# Steering_Wheel_V2_3.net
KiCad netlist of a schematic drawn in EAGLE
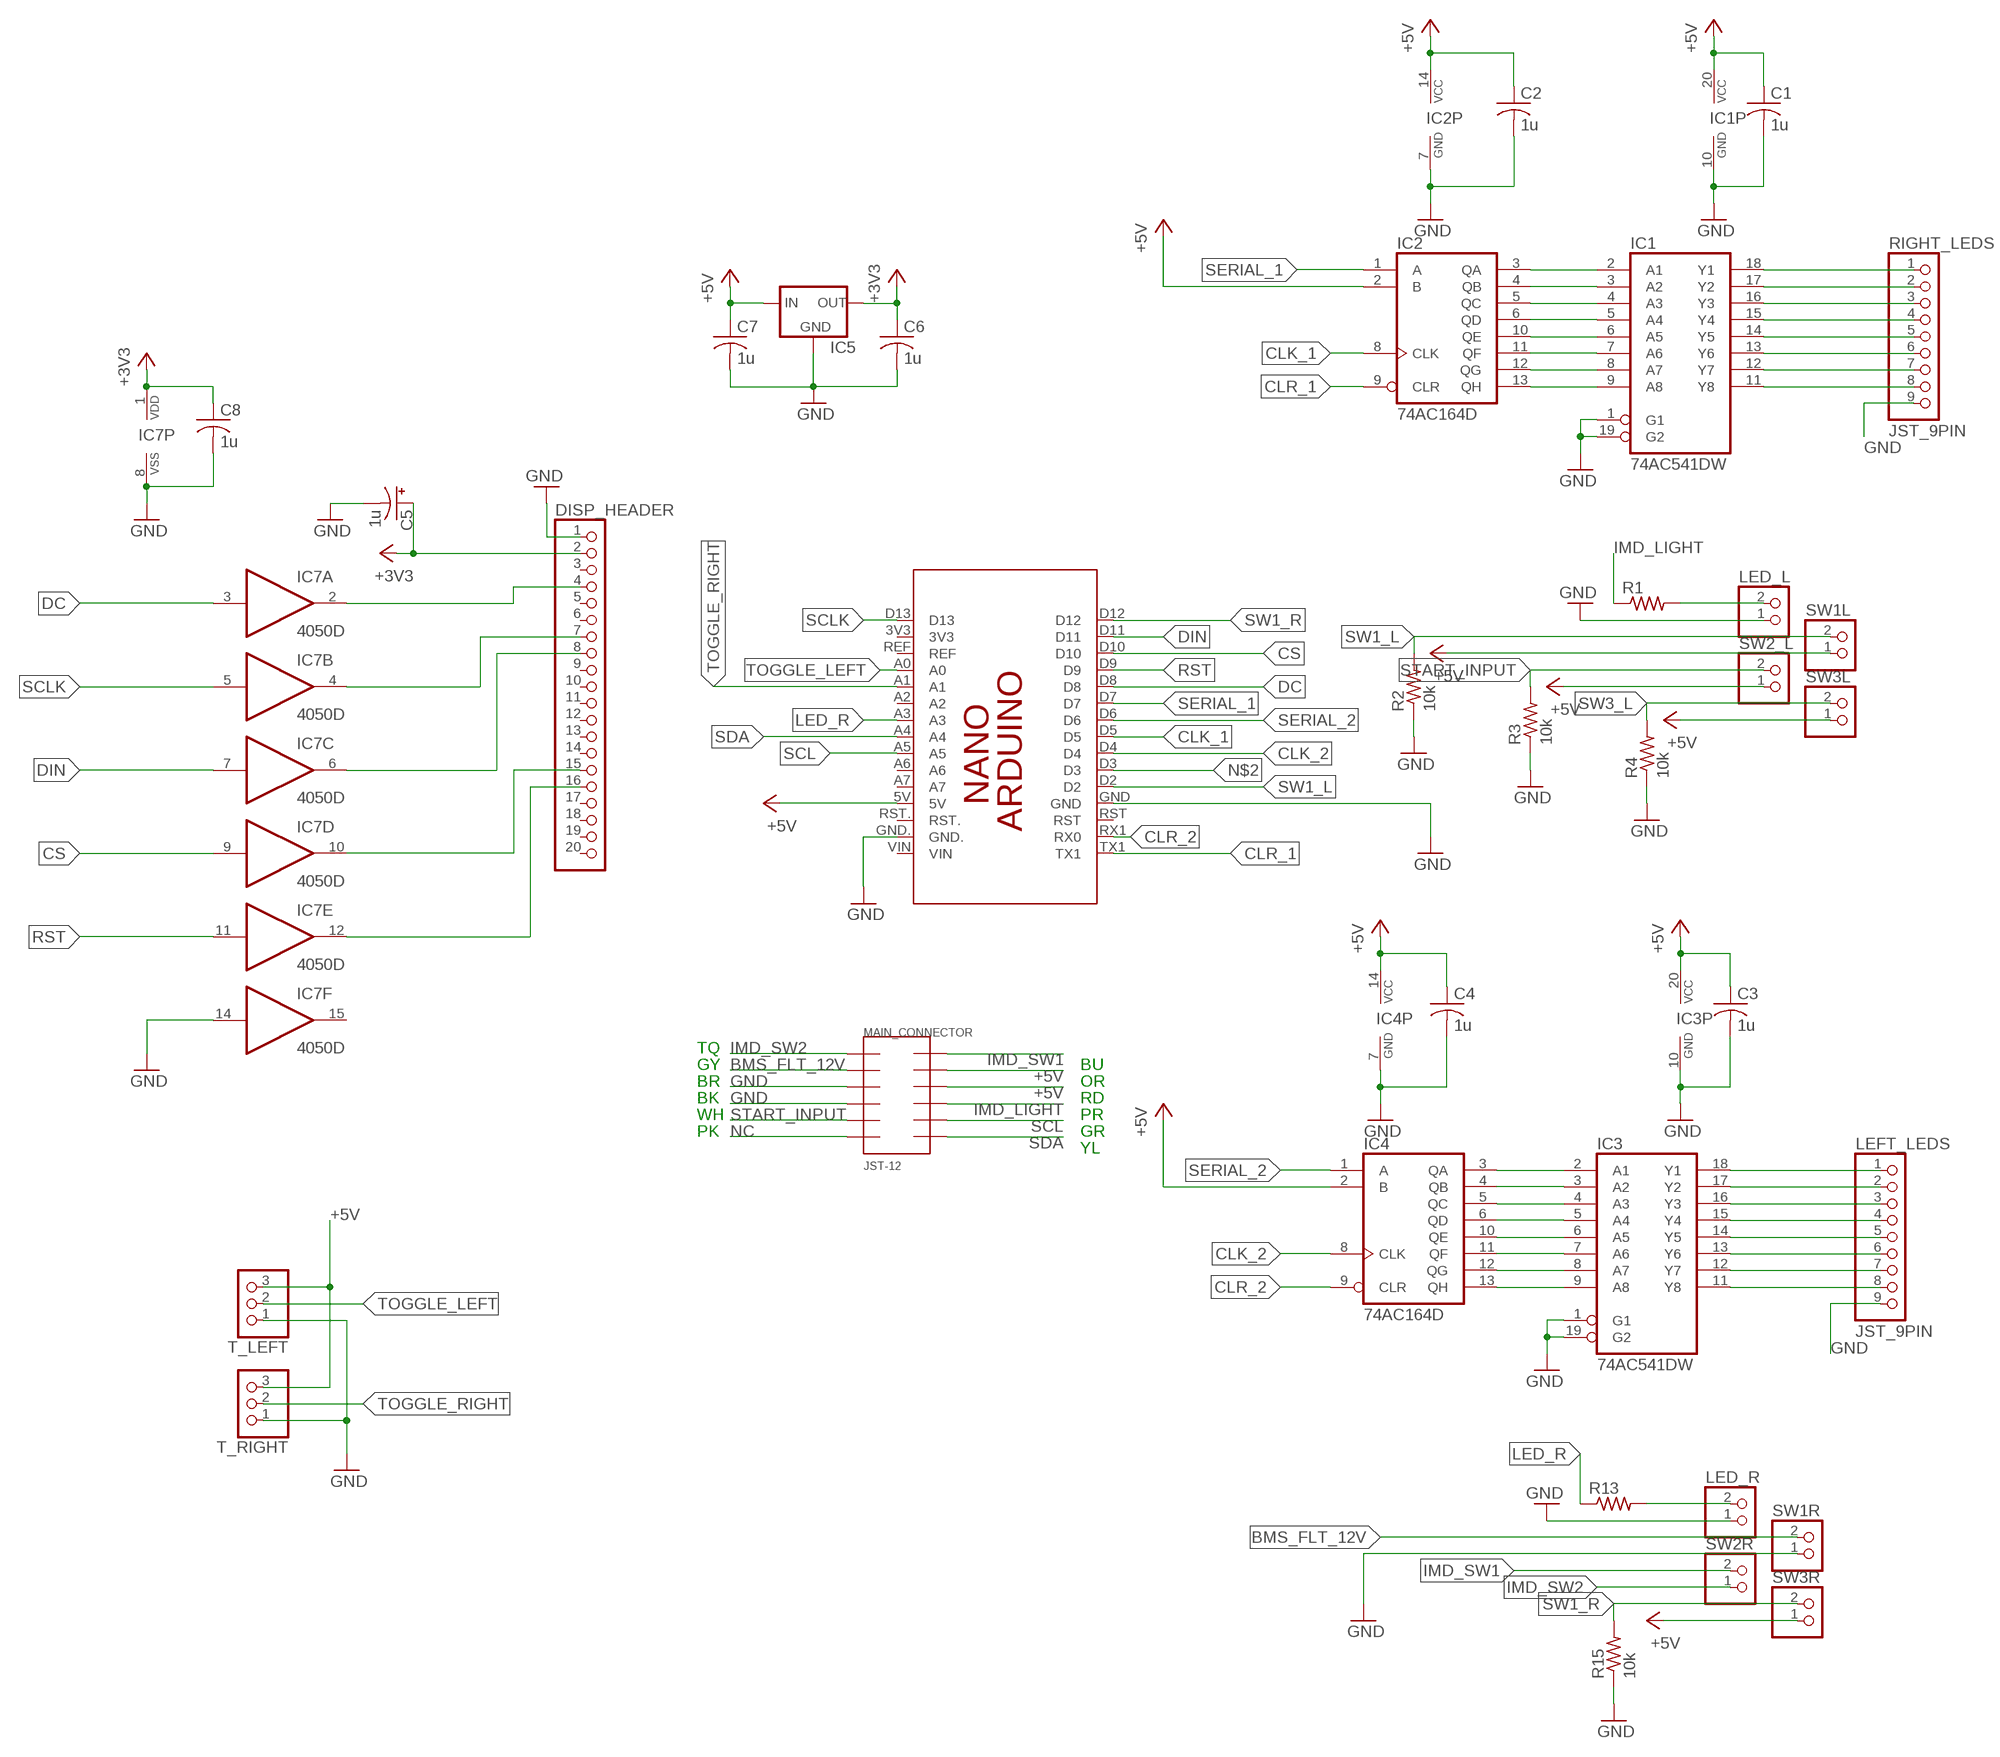
[diagram p0: schematic, sheet 1]

(export (version "E")
  (design (tool "Eeschema 10.0.6"))
  (components
    (comp (ref "C1")
      (value "1u")
      (footprint "eagle-import:C1206")
      (libsource (lib "eagle-import") (part "C-USC1206"))
    )
    (comp (ref "C2")
      (value "1u")
      (footprint "eagle-import:C1206")
      (libsource (lib "eagle-import") (part "C-USC1206"))
    )
    (comp (ref "C3")
      (value "1u")
      (footprint "eagle-import:C1206")
      (libsource (lib "eagle-import") (part "C-USC1206"))
    )
    (comp (ref "C4")
      (value "1u")
      (footprint "eagle-import:C1206")
      (libsource (lib "eagle-import") (part "C-USC1206"))
    )
    (comp (ref "C5")
      (value "1u")
      (footprint "eagle-import:E3,5-8")
      (libsource (lib "eagle-import") (part "CPOL-USE3.5-8"))
    )
    (comp (ref "C6")
      (value "1u")
      (footprint "eagle-import:C1206")
      (libsource (lib "eagle-import") (part "C-USC1206"))
    )
    (comp (ref "C7")
      (value "1u")
      (footprint "eagle-import:C1206")
      (libsource (lib "eagle-import") (part "C-USC1206"))
    )
    (comp (ref "C8")
      (value "1u")
      (footprint "eagle-import:C1206")
      (libsource (lib "eagle-import") (part "C-USC1206"))
    )
    (comp (ref "DISP_HEADER")
      (value "PINHD-1X20")
      (footprint "eagle-import:1X20")
      (libsource (lib "eagle-import") (part "PINHD-1X20"))
    )
    (comp (ref "IC1")
      (value "74AC541DW")
      (footprint "eagle-import:SO20W")
      (libsource (lib "eagle-import") (part "74541DWAC"))
    )
    (comp (ref "IC2")
      (value "74AC164D")
      (footprint "eagle-import:SO14")
      (libsource (lib "eagle-import") (part "74164DAC"))
    )
    (comp (ref "IC3")
      (value "74AC541DW")
      (footprint "eagle-import:SO20W")
      (libsource (lib "eagle-import") (part "74541DWAC"))
    )
    (comp (ref "IC4")
      (value "74AC164D")
      (footprint "eagle-import:SO14")
      (libsource (lib "eagle-import") (part "74164DAC"))
    )
    (comp (ref "IC5")
      (value "78XXL")
      (footprint "eagle-import:78XXL")
      (libsource (lib "eagle-import") (part "78XXL"))
    )
    (comp (ref "IC7")
      (value "4050D")
      (footprint "eagle-import:SO16")
      (libsource (lib "eagle-import") (part "4050D"))
    )
    (comp (ref "LED_L")
      (value "JST_2PIN-THM")
      (footprint "eagle-import:JST-PH-2-THM")
      (libsource (lib "eagle-import") (part "JST_2PIN-THM"))
    )
    (comp (ref "LED_R")
      (value "JST_2PIN-THM")
      (footprint "eagle-import:JST-PH-2-THM")
      (libsource (lib "eagle-import") (part "JST_2PIN-THM"))
    )
    (comp (ref "LEFT_LEDS")
      (value "JST_9PIN")
      (footprint "eagle-import:JST-PH-9-THM")
      (libsource (lib "eagle-import") (part "JST_9PIN"))
    )
    (comp (ref "MAIN_CONNECTOR")
      (value "JST-12")
      (footprint "eagle-import:PHD-12")
      (libsource (lib "eagle-import") (part "JST-12"))
    )
    (comp (ref "PCB1")
      (value "ARDUINO_NANO")
      (footprint "eagle-import:ARDUINO_NANO")
      (libsource (lib "eagle-import") (part "ARDUINO_NANO"))
    )
    (comp (ref "R1")
      (value "R-US_M1206")
      (footprint "eagle-import:M1206")
      (libsource (lib "eagle-import") (part "R-US_M1206"))
    )
    (comp (ref "R2")
      (value "10k")
      (footprint "eagle-import:M1206")
      (libsource (lib "eagle-import") (part "R-US_M1206"))
    )
    (comp (ref "R3")
      (value "10k")
      (footprint "eagle-import:M1206")
      (libsource (lib "eagle-import") (part "R-US_M1206"))
    )
    (comp (ref "R4")
      (value "10k")
      (footprint "eagle-import:M1206")
      (libsource (lib "eagle-import") (part "R-US_M1206"))
    )
    (comp (ref "R13")
      (value "R-US_M1206")
      (footprint "eagle-import:M1206")
      (libsource (lib "eagle-import") (part "R-US_M1206"))
    )
    (comp (ref "R15")
      (value "10k")
      (footprint "eagle-import:M1206")
      (libsource (lib "eagle-import") (part "R-US_M1206"))
    )
    (comp (ref "RIGHT_LEDS")
      (value "JST_9PIN")
      (footprint "eagle-import:JST-PH-9-THM")
      (libsource (lib "eagle-import") (part "JST_9PIN"))
    )
    (comp (ref "SW1L")
      (value "JST_2PIN-THM")
      (footprint "eagle-import:JST-PH-2-THM")
      (libsource (lib "eagle-import") (part "JST_2PIN-THM"))
    )
    (comp (ref "SW1R")
      (value "JST_2PIN-THM")
      (footprint "eagle-import:JST-PH-2-THM")
      (libsource (lib "eagle-import") (part "JST_2PIN-THM"))
    )
    (comp (ref "SW2R")
      (value "JST_2PIN-THM")
      (footprint "eagle-import:JST-PH-2-THM")
      (libsource (lib "eagle-import") (part "JST_2PIN-THM"))
    )
    (comp (ref "SW2_L")
      (value "JST_2PIN-THM")
      (footprint "eagle-import:JST-PH-2-THM")
      (libsource (lib "eagle-import") (part "JST_2PIN-THM"))
    )
    (comp (ref "SW3L")
      (value "JST_2PIN-THM")
      (footprint "eagle-import:JST-PH-2-THM")
      (libsource (lib "eagle-import") (part "JST_2PIN-THM"))
    )
    (comp (ref "SW3R")
      (value "JST_2PIN-THM")
      (footprint "eagle-import:JST-PH-2-THM")
      (libsource (lib "eagle-import") (part "JST_2PIN-THM"))
    )
    (comp (ref "T_LEFT")
      (value "JST_3PIN")
      (footprint "eagle-import:JST-PH-3-THM")
      (libsource (lib "eagle-import") (part "JST_3PIN"))
    )
    (comp (ref "T_RIGHT")
      (value "JST_3PIN")
      (footprint "eagle-import:JST-PH-3-THM")
      (libsource (lib "eagle-import") (part "JST_3PIN"))
    )
  )
  (nets
    (net (code "1") (name "+3V3") (class "Default")
      (node (ref "C5") (pin "+") (pinfunction "+_+") (pintype "passive"))
      (node (ref "C6") (pin "1") (pinfunction "1_1") (pintype "passive"))
      (node (ref "C8") (pin "1") (pinfunction "1_1") (pintype "passive"))
      (node (ref "DISP_HEADER") (pin "2") (pinfunction "2_2") (pintype "passive"))
      (node (ref "IC5") (pin "OUT") (pinfunction "OUT_OUT") (pintype "passive"))
      (node (ref "IC7") (pin "1") (pinfunction "VDD_1") (pintype "power_in"))
    )
    (net (code "2") (name "+5V") (class "Default")
      (node (ref "C1") (pin "1") (pinfunction "1_1") (pintype "passive"))
      (node (ref "C2") (pin "1") (pinfunction "1_1") (pintype "passive"))
      (node (ref "C3") (pin "1") (pinfunction "1_1") (pintype "passive"))
      (node (ref "C4") (pin "1") (pinfunction "1_1") (pintype "passive"))
      (node (ref "C7") (pin "1") (pinfunction "1_1") (pintype "passive"))
      (node (ref "IC1") (pin "20") (pinfunction "VCC_20") (pintype "power_in"))
      (node (ref "IC2") (pin "14") (pinfunction "VCC_14") (pintype "power_in"))
      (node (ref "IC2") (pin "2") (pinfunction "B_2") (pintype "input"))
      (node (ref "IC3") (pin "20") (pinfunction "VCC_20") (pintype "power_in"))
      (node (ref "IC4") (pin "14") (pinfunction "VCC_14") (pintype "power_in"))
      (node (ref "IC4") (pin "2") (pinfunction "B_2") (pintype "input"))
      (node (ref "IC5") (pin "IN") (pinfunction "IN_IN") (pintype "input"))
      (node (ref "MAIN_CONNECTOR") (pin "10") (pinfunction "10_10") (pintype "bidirectional"))
      (node (ref "MAIN_CONNECTOR") (pin "11") (pinfunction "11_11") (pintype "bidirectional"))
      (node (ref "PCB1") (pin "5V") (pinfunction "5V_5V") (pintype "bidirectional"))
      (node (ref "SW1L") (pin "1") (pinfunction "2_1") (pintype "passive"))
      (node (ref "SW2_L") (pin "1") (pinfunction "2_1") (pintype "passive"))
      (node (ref "SW3L") (pin "1") (pinfunction "2_1") (pintype "passive"))
      (node (ref "SW3R") (pin "1") (pinfunction "2_1") (pintype "passive"))
      (node (ref "T_LEFT") (pin "3") (pinfunction "3_3") (pintype "passive"))
      (node (ref "T_RIGHT") (pin "3") (pinfunction "3_3") (pintype "passive"))
    )
    (net (code "3") (name "/IMD_LIGHT") (class "Default")
      (node (ref "MAIN_CONNECTOR") (pin "9") (pinfunction "9_9") (pintype "bidirectional"))
      (node (ref "R1") (pin "1") (pinfunction "1_1") (pintype "passive"))
    )
    (net (code "4") (name "/NC") (class "Default")
      (node (ref "MAIN_CONNECTOR") (pin "6") (pinfunction "6_6") (pintype "bidirectional"))
    )
    (net (code "5") (name "BMS_FLT_12V") (class "Default")
      (node (ref "MAIN_CONNECTOR") (pin "2") (pinfunction "2_2") (pintype "bidirectional"))
      (node (ref "SW1R") (pin "2") (pinfunction "1_2") (pintype "passive"))
    )
    (net (code "6") (name "CLK_1") (class "Default")
      (node (ref "IC2") (pin "8") (pinfunction "CLK_8") (pintype "input"))
      (node (ref "PCB1") (pin "D5") (pinfunction "D5_D5") (pintype "bidirectional"))
    )
    (net (code "7") (name "CLK_2") (class "Default")
      (node (ref "IC4") (pin "8") (pinfunction "CLK_8") (pintype "input"))
      (node (ref "PCB1") (pin "D4") (pinfunction "D4_D4") (pintype "bidirectional"))
    )
    (net (code "8") (name "CLR_1") (class "Default")
      (node (ref "IC2") (pin "9") (pinfunction "CLR_9") (pintype "input"))
      (node (ref "PCB1") (pin "TX1") (pinfunction "TX1_TX1") (pintype "bidirectional"))
    )
    (net (code "9") (name "CLR_2") (class "Default")
      (node (ref "IC4") (pin "9") (pinfunction "CLR_9") (pintype "input"))
      (node (ref "PCB1") (pin "RX1") (pinfunction "RX0_RX1") (pintype "bidirectional"))
    )
    (net (code "10") (name "CS") (class "Default")
      (node (ref "IC7") (pin "9") (pinfunction "I_9") (pintype "input"))
      (node (ref "PCB1") (pin "D10") (pinfunction "D10_D10") (pintype "bidirectional"))
    )
    (net (code "11") (name "DC") (class "Default")
      (node (ref "IC7") (pin "3") (pinfunction "I_3") (pintype "input"))
      (node (ref "PCB1") (pin "D8") (pinfunction "D8_D8") (pintype "bidirectional"))
    )
    (net (code "12") (name "DIN") (class "Default")
      (node (ref "IC7") (pin "7") (pinfunction "I_7") (pintype "input"))
      (node (ref "PCB1") (pin "D11") (pinfunction "D11_D11") (pintype "bidirectional"))
    )
    (net (code "13") (name "GND") (class "Default")
      (node (ref "C1") (pin "2") (pinfunction "2_2") (pintype "passive"))
      (node (ref "C2") (pin "2") (pinfunction "2_2") (pintype "passive"))
      (node (ref "C3") (pin "2") (pinfunction "2_2") (pintype "passive"))
      (node (ref "C4") (pin "2") (pinfunction "2_2") (pintype "passive"))
      (node (ref "C5") (pin "-") (pinfunction "-_-") (pintype "passive"))
      (node (ref "C6") (pin "2") (pinfunction "2_2") (pintype "passive"))
      (node (ref "C7") (pin "2") (pinfunction "2_2") (pintype "passive"))
      (node (ref "C8") (pin "2") (pinfunction "2_2") (pintype "passive"))
      (node (ref "DISP_HEADER") (pin "1") (pinfunction "1_1") (pintype "passive"))
      (node (ref "IC1") (pin "1") (pinfunction "G1_1") (pintype "input"))
      (node (ref "IC1") (pin "10") (pinfunction "GND_10") (pintype "power_in"))
      (node (ref "IC1") (pin "19") (pinfunction "G2_19") (pintype "input"))
      (node (ref "IC2") (pin "7") (pinfunction "GND_7") (pintype "power_in"))
      (node (ref "IC3") (pin "1") (pinfunction "G1_1") (pintype "input"))
      (node (ref "IC3") (pin "10") (pinfunction "GND_10") (pintype "power_in"))
      (node (ref "IC3") (pin "19") (pinfunction "G2_19") (pintype "input"))
      (node (ref "IC4") (pin "7") (pinfunction "GND_7") (pintype "power_in"))
      (node (ref "IC5") (pin "GND") (pinfunction "GND_GND") (pintype "input"))
      (node (ref "IC7") (pin "14") (pinfunction "I_14") (pintype "input"))
      (node (ref "IC7") (pin "8") (pinfunction "VSS_8") (pintype "power_in"))
      (node (ref "LED_L") (pin "1") (pinfunction "2_1") (pintype "passive"))
      (node (ref "LED_R") (pin "1") (pinfunction "2_1") (pintype "passive"))
      (node (ref "LEFT_LEDS") (pin "9") (pinfunction "9_9") (pintype "passive"))
      (node (ref "MAIN_CONNECTOR") (pin "3") (pinfunction "3_3") (pintype "bidirectional"))
      (node (ref "MAIN_CONNECTOR") (pin "4") (pinfunction "4_4") (pintype "bidirectional"))
      (node (ref "PCB1") (pin "GND") (pinfunction "GND_GND") (pintype "bidirectional"))
      (node (ref "PCB1") (pin "GND.") (pinfunction "GND._GND.") (pintype "bidirectional"))
      (node (ref "R15") (pin "1") (pinfunction "1_1") (pintype "passive"))
      (node (ref "R2") (pin "1") (pinfunction "1_1") (pintype "passive"))
      (node (ref "R3") (pin "1") (pinfunction "1_1") (pintype "passive"))
      (node (ref "R4") (pin "1") (pinfunction "1_1") (pintype "passive"))
      (node (ref "RIGHT_LEDS") (pin "9") (pinfunction "9_9") (pintype "passive"))
      (node (ref "SW1R") (pin "1") (pinfunction "2_1") (pintype "passive"))
      (node (ref "T_LEFT") (pin "1") (pinfunction "1_1") (pintype "passive"))
      (node (ref "T_RIGHT") (pin "1") (pinfunction "1_1") (pintype "passive"))
    )
    (net (code "14") (name "IMD_SW1") (class "Default")
      (node (ref "MAIN_CONNECTOR") (pin "12") (pinfunction "12_12") (pintype "bidirectional"))
      (node (ref "SW2R") (pin "2") (pinfunction "1_2") (pintype "passive"))
    )
    (net (code "15") (name "IMD_SW2") (class "Default")
      (node (ref "MAIN_CONNECTOR") (pin "1") (pinfunction "1_1") (pintype "bidirectional"))
      (node (ref "SW2R") (pin "1") (pinfunction "2_1") (pintype "passive"))
    )
    (net (code "16") (name "LED_R") (class "Default")
      (node (ref "PCB1") (pin "A3") (pinfunction "A3_A3") (pintype "bidirectional"))
      (node (ref "R13") (pin "1") (pinfunction "1_1") (pintype "passive"))
    )
    (net (code "17") (name "N$2") (class "Default")
      (node (ref "PCB1") (pin "D3") (pinfunction "D3_D3") (pintype "bidirectional"))
    )
    (net (code "18") (name "Net-(IC1A-A1)") (class "Default")
      (node (ref "IC1") (pin "2") (pinfunction "A1_2") (pintype "input"))
      (node (ref "IC2") (pin "3") (pinfunction "QA_3") (pintype "output"))
    )
    (net (code "19") (name "Net-(IC1A-A2)") (class "Default")
      (node (ref "IC1") (pin "3") (pinfunction "A2_3") (pintype "input"))
      (node (ref "IC2") (pin "4") (pinfunction "QB_4") (pintype "output"))
    )
    (net (code "20") (name "Net-(IC1A-A3)") (class "Default")
      (node (ref "IC1") (pin "4") (pinfunction "A3_4") (pintype "input"))
      (node (ref "IC2") (pin "5") (pinfunction "QC_5") (pintype "output"))
    )
    (net (code "21") (name "Net-(IC1A-A4)") (class "Default")
      (node (ref "IC1") (pin "5") (pinfunction "A4_5") (pintype "input"))
      (node (ref "IC2") (pin "6") (pinfunction "QD_6") (pintype "output"))
    )
    (net (code "22") (name "Net-(IC1A-A5)") (class "Default")
      (node (ref "IC1") (pin "6") (pinfunction "A5_6") (pintype "input"))
      (node (ref "IC2") (pin "10") (pinfunction "QE_10") (pintype "output"))
    )
    (net (code "23") (name "Net-(IC1A-A6)") (class "Default")
      (node (ref "IC1") (pin "7") (pinfunction "A6_7") (pintype "input"))
      (node (ref "IC2") (pin "11") (pinfunction "QF_11") (pintype "output"))
    )
    (net (code "24") (name "Net-(IC1A-A7)") (class "Default")
      (node (ref "IC1") (pin "8") (pinfunction "A7_8") (pintype "input"))
      (node (ref "IC2") (pin "12") (pinfunction "QG_12") (pintype "output"))
    )
    (net (code "25") (name "Net-(IC1A-A8)") (class "Default")
      (node (ref "IC1") (pin "9") (pinfunction "A8_9") (pintype "input"))
      (node (ref "IC2") (pin "13") (pinfunction "QH_13") (pintype "output"))
    )
    (net (code "26") (name "Net-(IC1A-Y1)") (class "Default")
      (node (ref "IC1") (pin "18") (pinfunction "Y1_18") (pintype "tri_state"))
      (node (ref "RIGHT_LEDS") (pin "1") (pinfunction "1_1") (pintype "passive"))
    )
    (net (code "27") (name "Net-(IC1A-Y2)") (class "Default")
      (node (ref "IC1") (pin "17") (pinfunction "Y2_17") (pintype "tri_state"))
      (node (ref "RIGHT_LEDS") (pin "2") (pinfunction "2_2") (pintype "passive"))
    )
    (net (code "28") (name "Net-(IC1A-Y3)") (class "Default")
      (node (ref "IC1") (pin "16") (pinfunction "Y3_16") (pintype "tri_state"))
      (node (ref "RIGHT_LEDS") (pin "3") (pinfunction "3_3") (pintype "passive"))
    )
    (net (code "29") (name "Net-(IC1A-Y4)") (class "Default")
      (node (ref "IC1") (pin "15") (pinfunction "Y4_15") (pintype "tri_state"))
      (node (ref "RIGHT_LEDS") (pin "4") (pinfunction "4_4") (pintype "passive"))
    )
    (net (code "30") (name "Net-(IC1A-Y5)") (class "Default")
      (node (ref "IC1") (pin "14") (pinfunction "Y5_14") (pintype "tri_state"))
      (node (ref "RIGHT_LEDS") (pin "5") (pinfunction "5_5") (pintype "passive"))
    )
    (net (code "31") (name "Net-(IC1A-Y6)") (class "Default")
      (node (ref "IC1") (pin "13") (pinfunction "Y6_13") (pintype "tri_state"))
      (node (ref "RIGHT_LEDS") (pin "6") (pinfunction "6_6") (pintype "passive"))
    )
    (net (code "32") (name "Net-(IC1A-Y7)") (class "Default")
      (node (ref "IC1") (pin "12") (pinfunction "Y7_12") (pintype "tri_state"))
      (node (ref "RIGHT_LEDS") (pin "7") (pinfunction "7_7") (pintype "passive"))
    )
    (net (code "33") (name "Net-(IC1A-Y8)") (class "Default")
      (node (ref "IC1") (pin "11") (pinfunction "Y8_11") (pintype "tri_state"))
      (node (ref "RIGHT_LEDS") (pin "8") (pinfunction "8_8") (pintype "passive"))
    )
    (net (code "34") (name "Net-(IC3A-A1)") (class "Default")
      (node (ref "IC3") (pin "2") (pinfunction "A1_2") (pintype "input"))
      (node (ref "IC4") (pin "3") (pinfunction "QA_3") (pintype "output"))
    )
    (net (code "35") (name "Net-(IC3A-A2)") (class "Default")
      (node (ref "IC3") (pin "3") (pinfunction "A2_3") (pintype "input"))
      (node (ref "IC4") (pin "4") (pinfunction "QB_4") (pintype "output"))
    )
    (net (code "36") (name "Net-(IC3A-A3)") (class "Default")
      (node (ref "IC3") (pin "4") (pinfunction "A3_4") (pintype "input"))
      (node (ref "IC4") (pin "5") (pinfunction "QC_5") (pintype "output"))
    )
    (net (code "37") (name "Net-(IC3A-A4)") (class "Default")
      (node (ref "IC3") (pin "5") (pinfunction "A4_5") (pintype "input"))
      (node (ref "IC4") (pin "6") (pinfunction "QD_6") (pintype "output"))
    )
    (net (code "38") (name "Net-(IC3A-A5)") (class "Default")
      (node (ref "IC3") (pin "6") (pinfunction "A5_6") (pintype "input"))
      (node (ref "IC4") (pin "10") (pinfunction "QE_10") (pintype "output"))
    )
    (net (code "39") (name "Net-(IC3A-A6)") (class "Default")
      (node (ref "IC3") (pin "7") (pinfunction "A6_7") (pintype "input"))
      (node (ref "IC4") (pin "11") (pinfunction "QF_11") (pintype "output"))
    )
    (net (code "40") (name "Net-(IC3A-A7)") (class "Default")
      (node (ref "IC3") (pin "8") (pinfunction "A7_8") (pintype "input"))
      (node (ref "IC4") (pin "12") (pinfunction "QG_12") (pintype "output"))
    )
    (net (code "41") (name "Net-(IC3A-A8)") (class "Default")
      (node (ref "IC3") (pin "9") (pinfunction "A8_9") (pintype "input"))
      (node (ref "IC4") (pin "13") (pinfunction "QH_13") (pintype "output"))
    )
    (net (code "42") (name "Net-(IC3A-Y1)") (class "Default")
      (node (ref "IC3") (pin "18") (pinfunction "Y1_18") (pintype "tri_state"))
      (node (ref "LEFT_LEDS") (pin "1") (pinfunction "1_1") (pintype "passive"))
    )
    (net (code "43") (name "Net-(IC3A-Y2)") (class "Default")
      (node (ref "IC3") (pin "17") (pinfunction "Y2_17") (pintype "tri_state"))
      (node (ref "LEFT_LEDS") (pin "2") (pinfunction "2_2") (pintype "passive"))
    )
    (net (code "44") (name "Net-(IC3A-Y3)") (class "Default")
      (node (ref "IC3") (pin "16") (pinfunction "Y3_16") (pintype "tri_state"))
      (node (ref "LEFT_LEDS") (pin "3") (pinfunction "3_3") (pintype "passive"))
    )
    (net (code "45") (name "Net-(IC3A-Y4)") (class "Default")
      (node (ref "IC3") (pin "15") (pinfunction "Y4_15") (pintype "tri_state"))
      (node (ref "LEFT_LEDS") (pin "4") (pinfunction "4_4") (pintype "passive"))
    )
    (net (code "46") (name "Net-(IC3A-Y5)") (class "Default")
      (node (ref "IC3") (pin "14") (pinfunction "Y5_14") (pintype "tri_state"))
      (node (ref "LEFT_LEDS") (pin "5") (pinfunction "5_5") (pintype "passive"))
    )
    (net (code "47") (name "Net-(IC3A-Y6)") (class "Default")
      (node (ref "IC3") (pin "13") (pinfunction "Y6_13") (pintype "tri_state"))
      (node (ref "LEFT_LEDS") (pin "6") (pinfunction "6_6") (pintype "passive"))
    )
    (net (code "48") (name "Net-(IC3A-Y7)") (class "Default")
      (node (ref "IC3") (pin "12") (pinfunction "Y7_12") (pintype "tri_state"))
      (node (ref "LEFT_LEDS") (pin "7") (pinfunction "7_7") (pintype "passive"))
    )
    (net (code "49") (name "Net-(IC3A-Y8)") (class "Default")
      (node (ref "IC3") (pin "11") (pinfunction "Y8_11") (pintype "tri_state"))
      (node (ref "LEFT_LEDS") (pin "8") (pinfunction "8_8") (pintype "passive"))
    )
    (net (code "50") (name "Net-(IC7A-O)") (class "Default")
      (node (ref "DISP_HEADER") (pin "4") (pinfunction "4_4") (pintype "passive"))
      (node (ref "IC7") (pin "2") (pinfunction "O_2") (pintype "output"))
    )
    (net (code "51") (name "Net-(IC7B-O)") (class "Default")
      (node (ref "DISP_HEADER") (pin "7") (pinfunction "7_7") (pintype "passive"))
      (node (ref "IC7") (pin "4") (pinfunction "O_4") (pintype "output"))
    )
    (net (code "52") (name "Net-(IC7C-O)") (class "Default")
      (node (ref "DISP_HEADER") (pin "8") (pinfunction "8_8") (pintype "passive"))
      (node (ref "IC7") (pin "6") (pinfunction "O_6") (pintype "output"))
    )
    (net (code "53") (name "Net-(IC7D-O)") (class "Default")
      (node (ref "DISP_HEADER") (pin "15") (pinfunction "15_15") (pintype "passive"))
      (node (ref "IC7") (pin "10") (pinfunction "O_10") (pintype "output"))
    )
    (net (code "54") (name "Net-(IC7E-O)") (class "Default")
      (node (ref "DISP_HEADER") (pin "16") (pinfunction "16_16") (pintype "passive"))
      (node (ref "IC7") (pin "12") (pinfunction "O_12") (pintype "output"))
    )
    (net (code "55") (name "Net-(LED_L-1)") (class "Default")
      (node (ref "LED_L") (pin "2") (pinfunction "1_2") (pintype "passive"))
      (node (ref "R1") (pin "2") (pinfunction "2_2") (pintype "passive"))
    )
    (net (code "56") (name "Net-(LED_R-1)") (class "Default")
      (node (ref "LED_R") (pin "2") (pinfunction "1_2") (pintype "passive"))
      (node (ref "R13") (pin "2") (pinfunction "2_2") (pintype "passive"))
    )
    (net (code "57") (name "RST") (class "Default")
      (node (ref "IC7") (pin "11") (pinfunction "I_11") (pintype "input"))
      (node (ref "PCB1") (pin "D9") (pinfunction "D9_D9") (pintype "bidirectional"))
    )
    (net (code "58") (name "SCL") (class "Default")
      (node (ref "MAIN_CONNECTOR") (pin "8") (pinfunction "8_8") (pintype "bidirectional"))
      (node (ref "PCB1") (pin "A5") (pinfunction "A5_A5") (pintype "bidirectional"))
    )
    (net (code "59") (name "SCLK") (class "Default")
      (node (ref "IC7") (pin "5") (pinfunction "I_5") (pintype "input"))
      (node (ref "PCB1") (pin "D13") (pinfunction "D13_D13") (pintype "bidirectional"))
    )
    (net (code "60") (name "SDA") (class "Default")
      (node (ref "MAIN_CONNECTOR") (pin "7") (pinfunction "7_7") (pintype "bidirectional"))
      (node (ref "PCB1") (pin "A4") (pinfunction "A4_A4") (pintype "bidirectional"))
    )
    (net (code "61") (name "SERIAL_1") (class "Default")
      (node (ref "IC2") (pin "1") (pinfunction "A_1") (pintype "input"))
      (node (ref "PCB1") (pin "D7") (pinfunction "D7_D7") (pintype "bidirectional"))
    )
    (net (code "62") (name "SERIAL_2") (class "Default")
      (node (ref "IC4") (pin "1") (pinfunction "A_1") (pintype "input"))
      (node (ref "PCB1") (pin "D6") (pinfunction "D6_D6") (pintype "bidirectional"))
    )
    (net (code "63") (name "START_INPUT") (class "Default")
      (node (ref "MAIN_CONNECTOR") (pin "5") (pinfunction "5_5") (pintype "bidirectional"))
      (node (ref "R3") (pin "2") (pinfunction "2_2") (pintype "passive"))
      (node (ref "SW2_L") (pin "2") (pinfunction "1_2") (pintype "passive"))
    )
    (net (code "64") (name "SW1_L") (class "Default")
      (node (ref "PCB1") (pin "D2") (pinfunction "D2_D2") (pintype "bidirectional"))
      (node (ref "R2") (pin "2") (pinfunction "2_2") (pintype "passive"))
      (node (ref "SW1L") (pin "2") (pinfunction "1_2") (pintype "passive"))
    )
    (net (code "65") (name "SW1_R") (class "Default")
      (node (ref "PCB1") (pin "D12") (pinfunction "D12_D12") (pintype "bidirectional"))
      (node (ref "R15") (pin "2") (pinfunction "2_2") (pintype "passive"))
      (node (ref "SW3R") (pin "2") (pinfunction "1_2") (pintype "passive"))
    )
    (net (code "66") (name "SW3_L") (class "Default")
      (node (ref "R4") (pin "2") (pinfunction "2_2") (pintype "passive"))
      (node (ref "SW3L") (pin "2") (pinfunction "1_2") (pintype "passive"))
    )
    (net (code "67") (name "TOGGLE_LEFT") (class "Default")
      (node (ref "PCB1") (pin "A0") (pinfunction "A0_A0") (pintype "bidirectional"))
      (node (ref "T_LEFT") (pin "2") (pinfunction "2_2") (pintype "passive"))
    )
    (net (code "68") (name "TOGGLE_RIGHT") (class "Default")
      (node (ref "PCB1") (pin "A1") (pinfunction "A1_A1") (pintype "bidirectional"))
      (node (ref "T_RIGHT") (pin "2") (pinfunction "2_2") (pintype "passive"))
    )
    (net (code "69") (name "unconnected-(DISP_HEADER-Pad3)") (class "Default")
      (node (ref "DISP_HEADER") (pin "3") (pinfunction "3_3") (pintype "passive"))
    )
    (net (code "70") (name "unconnected-(DISP_HEADER-Pad5)") (class "Default")
      (node (ref "DISP_HEADER") (pin "5") (pinfunction "5_5") (pintype "passive"))
    )
    (net (code "71") (name "unconnected-(DISP_HEADER-Pad6)") (class "Default")
      (node (ref "DISP_HEADER") (pin "6") (pinfunction "6_6") (pintype "passive"))
    )
    (net (code "72") (name "unconnected-(DISP_HEADER-Pad9)") (class "Default")
      (node (ref "DISP_HEADER") (pin "9") (pinfunction "9_9") (pintype "passive"))
    )
    (net (code "73") (name "unconnected-(DISP_HEADER-Pad10)") (class "Default")
      (node (ref "DISP_HEADER") (pin "10") (pinfunction "10_10") (pintype "passive"))
    )
    (net (code "74") (name "unconnected-(DISP_HEADER-Pad11)") (class "Default")
      (node (ref "DISP_HEADER") (pin "11") (pinfunction "11_11") (pintype "passive"))
    )
    (net (code "75") (name "unconnected-(DISP_HEADER-Pad12)") (class "Default")
      (node (ref "DISP_HEADER") (pin "12") (pinfunction "12_12") (pintype "passive"))
    )
    (net (code "76") (name "unconnected-(DISP_HEADER-Pad13)") (class "Default")
      (node (ref "DISP_HEADER") (pin "13") (pinfunction "13_13") (pintype "passive"))
    )
    (net (code "77") (name "unconnected-(DISP_HEADER-Pad14)") (class "Default")
      (node (ref "DISP_HEADER") (pin "14") (pinfunction "14_14") (pintype "passive"))
    )
    (net (code "78") (name "unconnected-(DISP_HEADER-Pad17)") (class "Default")
      (node (ref "DISP_HEADER") (pin "17") (pinfunction "17_17") (pintype "passive"))
    )
    (net (code "79") (name "unconnected-(DISP_HEADER-Pad18)") (class "Default")
      (node (ref "DISP_HEADER") (pin "18") (pinfunction "18_18") (pintype "passive"))
    )
    (net (code "80") (name "unconnected-(DISP_HEADER-Pad19)") (class "Default")
      (node (ref "DISP_HEADER") (pin "19") (pinfunction "19_19") (pintype "passive"))
    )
    (net (code "81") (name "unconnected-(DISP_HEADER-Pad20)") (class "Default")
      (node (ref "DISP_HEADER") (pin "20") (pinfunction "20_20") (pintype "passive"))
    )
    (net (code "82") (name "unconnected-(IC7F-O-Pad15)") (class "Default")
      (node (ref "IC7") (pin "15") (pinfunction "O_15") (pintype "output"))
    )
    (net (code "83") (name "unconnected-(PCB1-Pad3V3)") (class "Default")
      (node (ref "PCB1") (pin "3V3") (pinfunction "3V3_3V3") (pintype "bidirectional"))
    )
    (net (code "84") (name "unconnected-(PCB1-PadA2)") (class "Default")
      (node (ref "PCB1") (pin "A2") (pinfunction "A2_A2") (pintype "bidirectional"))
    )
    (net (code "85") (name "unconnected-(PCB1-PadA6)") (class "Default")
      (node (ref "PCB1") (pin "A6") (pinfunction "A6_A6") (pintype "bidirectional"))
    )
    (net (code "86") (name "unconnected-(PCB1-PadA7)") (class "Default")
      (node (ref "PCB1") (pin "A7") (pinfunction "A7_A7") (pintype "bidirectional"))
    )
    (net (code "87") (name "unconnected-(PCB1-PadREF)") (class "Default")
      (node (ref "PCB1") (pin "REF") (pinfunction "REF_REF") (pintype "bidirectional"))
    )
    (net (code "88") (name "unconnected-(PCB1-PadRST)") (class "Default")
      (node (ref "PCB1") (pin "RST") (pinfunction "RST_RST") (pintype "bidirectional"))
    )
    (net (code "89") (name "unconnected-(PCB1-PadRST.)") (class "Default")
      (node (ref "PCB1") (pin "RST.") (pinfunction "RST._RST.") (pintype "bidirectional"))
    )
    (net (code "90") (name "unconnected-(PCB1-PadVIN)") (class "Default")
      (node (ref "PCB1") (pin "VIN") (pinfunction "VIN_VIN") (pintype "bidirectional"))
    )
  )
)
